# 13.net
KiCad netlist of a schematic drawn in Altium Designer
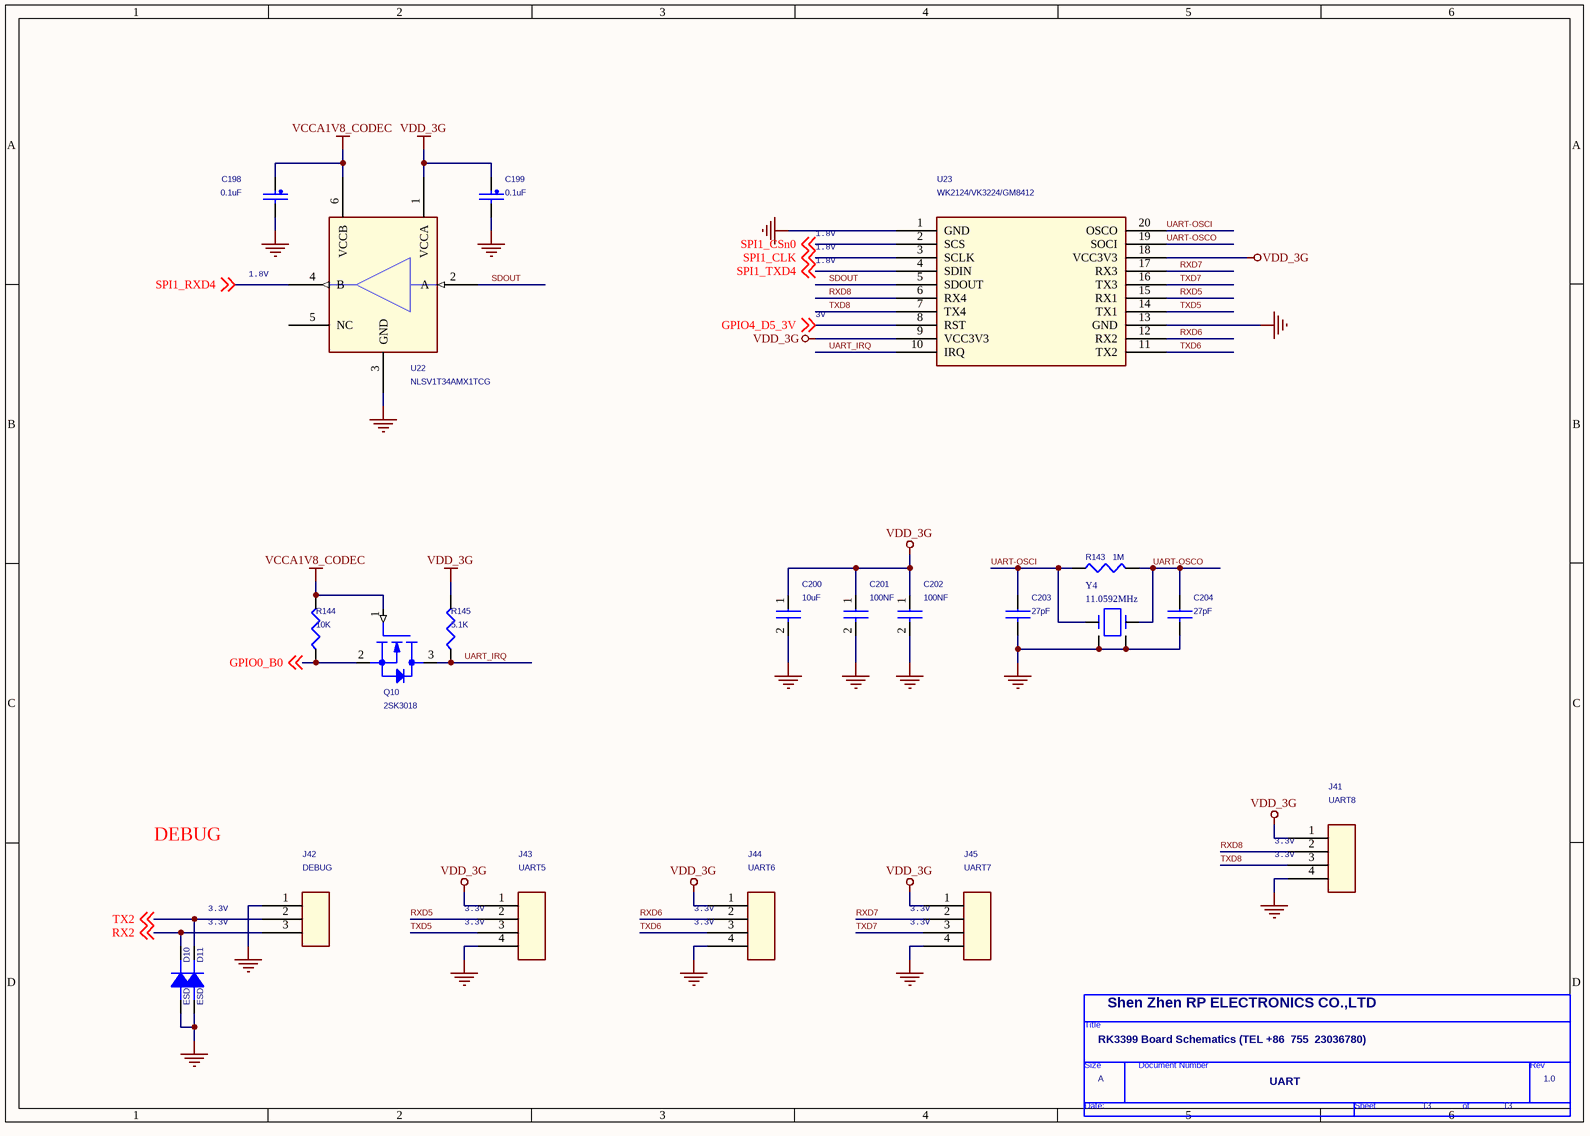
[diagram p0: 13.SchDoc]

(export (version "E")
  (design (tool "Eeschema 10.0.6"))
  (components
    (comp (ref "C198")
      (value "0.1uF")
      (description "CAP CER 0.22UF 6.3V 20% X5R 0201")
      (fields (field (name "TOLERANCE") "20%") (field (name "VOLTAGE") "6.3V"))
      (libsource (lib "*") (part "CAP_NP"))
    )
    (comp (ref "C199")
      (value "0.1uF")
      (description "CAP CER 0.22UF 10V 20% X5R 0201")
      (fields (field (name "VOLTAGE") "10V") (field (name "TOLERANCE") "20%"))
      (libsource (lib "*") (part "CAP_NP"))
    )
    (comp (ref "C200")
      (value "10uF")
      (footprint "0805C")
      (description "cap,10.00uF,+/-10%,10V,X5R,C0805")
      (fields
        (field (name "VOLTAGE") "10V")
        (field (name "TOLERANCE") "10%")
        (field (name "CREATED BY") "JJJ")
      )
      (libsource (lib "*") (part "CAP NP_Dup2"))
    )
    (comp (ref "C201")
      (value "100NF")
      (description "cap,100.00nF,+/-10%,16V,X5R,C0402")
      (fields
        (field (name "VOLTAGE") "16V")
        (field (name "MANUFACTURER") "TDK")
        (field (name "CREATED BY") "JJJ")
      )
      (libsource (lib "*") (part "CAP NP_Dup2"))
    )
    (comp (ref "C202")
      (value "100NF")
      (description "cap,100.00nF,+/-10%,16V,X5R,C0402")
      (fields
        (field (name "VOLTAGE") "16V")
        (field (name "MANUFACTURER") "TDK")
        (field (name "CREATED BY") "JJJ")
      )
      (libsource (lib "*") (part "CAP NP_Dup2"))
    )
    (comp (ref "C203") (value "27pF") (libsource (lib "*") (part "CAP NP_3_Dup1")))
    (comp (ref "C204") (value "27pF") (libsource (lib "*") (part "CAP NP_3_Dup1")))
    (comp (ref "D10") (value "ESD") (libsource (lib "*") (part "DIODE_Dup2")))
    (comp (ref "D11") (value "ESD") (libsource (lib "*") (part "DIODE_Dup2")))
    (comp (ref "J41") (value "UART8") (libsource (lib "*") (part "CON4")))
    (comp (ref "J42") (value "DEBUG") (libsource (lib "*") (part "CON4_1")))
    (comp (ref "J43") (value "UART5") (libsource (lib "*") (part "CON4")))
    (comp (ref "J44") (value "UART6") (libsource (lib "*") (part "CON4")))
    (comp (ref "J45") (value "UART7") (libsource (lib "*") (part "CON4")))
    (comp (ref "Q10") (value "2SK3018") (libsource (lib "*") (part "2N6756_0")))
    (comp (ref "R143") (value "1M") (footprint "0805") (libsource (lib "*") (part "RES_0")))
    (comp (ref "R144") (value "10K") (libsource (lib "*") (part "R_Dup1")))
    (comp (ref "R145") (value "5.1K") (libsource (lib "*") (part "R_Dup1")))
    (comp (ref "U22")
      (value "NLSV1T34AMX1TCG")
      (description "IC VXLTR 1 BIT DUAL-SUPPLY 0.9-4.5V 613AF")
      (libsource (lib "*") (part "NLSV1T34"))
    )
    (comp (ref "U23") (value "WK2124/VK3224/GM8412") (libsource (lib "*") (part "WK2124/VK3224/GM8412")))
    (comp (ref "Y4") (value "11.0592MHz") (libsource (lib "*") (part "CRYSTAL_2")))
  )
  (nets
    (net (code "1") (name "/RXD5") (class "Default")
      (node (ref "J43") (pin "2") (pinfunction "2_2") (pintype "passive"))
      (node (ref "U23") (pin "15") (pinfunction "RX1_15") (pintype "passive"))
    )
    (net (code "2") (name "/RXD6") (class "Default")
      (node (ref "J44") (pin "2") (pinfunction "2_2") (pintype "passive"))
      (node (ref "U23") (pin "12") (pinfunction "RX2_12") (pintype "passive"))
    )
    (net (code "3") (name "/RXD7") (class "Default")
      (node (ref "J45") (pin "2") (pinfunction "2_2") (pintype "passive"))
      (node (ref "U23") (pin "17") (pinfunction "RX3_17") (pintype "passive"))
    )
    (net (code "4") (name "/RXD8") (class "Default")
      (node (ref "J41") (pin "2") (pinfunction "2_2") (pintype "passive"))
      (node (ref "U23") (pin "6") (pinfunction "RX4_6") (pintype "passive"))
    )
    (net (code "5") (name "/SDOUT") (class "Default")
      (node (ref "U22") (pin "2") (pinfunction "A_2") (pintype "input"))
      (node (ref "U23") (pin "5") (pinfunction "SDOUT_5") (pintype "passive"))
    )
    (net (code "6") (name "/TXD5") (class "Default")
      (node (ref "J43") (pin "3") (pinfunction "3_3") (pintype "passive"))
      (node (ref "U23") (pin "14") (pinfunction "TX1_14") (pintype "passive"))
    )
    (net (code "7") (name "/TXD6") (class "Default")
      (node (ref "J44") (pin "3") (pinfunction "3_3") (pintype "passive"))
      (node (ref "U23") (pin "11") (pinfunction "TX2_11") (pintype "passive"))
    )
    (net (code "8") (name "/TXD7") (class "Default")
      (node (ref "J45") (pin "3") (pinfunction "3_3") (pintype "passive"))
      (node (ref "U23") (pin "16") (pinfunction "TX3_16") (pintype "passive"))
    )
    (net (code "9") (name "/TXD8") (class "Default")
      (node (ref "J41") (pin "3") (pinfunction "3_3") (pintype "passive"))
      (node (ref "U23") (pin "7") (pinfunction "TX4_7") (pintype "passive"))
    )
    (net (code "10") (name "/UART-OSCI") (class "Default")
      (node (ref "C203") (pin "1") (pinfunction "1_1") (pintype "passive"))
      (node (ref "R143") (pin "2") (pinfunction "2_2") (pintype "passive"))
      (node (ref "U23") (pin "20") (pinfunction "OSCO_20") (pintype "passive"))
      (node (ref "Y4") (pin "1") (pinfunction "1_1") (pintype "passive"))
    )
    (net (code "11") (name "/UART-OSCO") (class "Default")
      (node (ref "C204") (pin "1") (pinfunction "1_1") (pintype "passive"))
      (node (ref "R143") (pin "1") (pinfunction "1_1") (pintype "passive"))
      (node (ref "U23") (pin "19") (pinfunction "SOCI_19") (pintype "passive"))
      (node (ref "Y4") (pin "3") (pinfunction "3_3") (pintype "passive"))
    )
    (net (code "12") (name "/UART_IRQ") (class "Default")
      (node (ref "Q10") (pin "3") (pinfunction "DRAIN_3") (pintype "passive"))
      (node (ref "R145") (pin "2") (pinfunction "2_2") (pintype "passive"))
      (node (ref "U23") (pin "10") (pinfunction "IRQ_10") (pintype "passive"))
    )
    (net (code "13") (name "GND") (class "Default")
      (node (ref "C198") (pin "2") (pinfunction "2_2") (pintype "passive"))
      (node (ref "C199") (pin "2") (pinfunction "2_2") (pintype "passive"))
      (node (ref "C200") (pin "2") (pinfunction "2_2") (pintype "passive"))
      (node (ref "C201") (pin "2") (pinfunction "2_2") (pintype "passive"))
      (node (ref "C202") (pin "2") (pinfunction "2_2") (pintype "passive"))
      (node (ref "C203") (pin "2") (pinfunction "2_2") (pintype "passive"))
      (node (ref "C204") (pin "2") (pinfunction "2_2") (pintype "passive"))
      (node (ref "D10") (pin "1") (pinfunction "A_1") (pintype "passive"))
      (node (ref "D11") (pin "1") (pinfunction "A_1") (pintype "passive"))
      (node (ref "J41") (pin "4") (pinfunction "4_4") (pintype "passive"))
      (node (ref "J42") (pin "1") (pinfunction "1_1") (pintype "passive"))
      (node (ref "J43") (pin "4") (pinfunction "4_4") (pintype "passive"))
      (node (ref "J44") (pin "4") (pinfunction "4_4") (pintype "passive"))
      (node (ref "J45") (pin "4") (pinfunction "4_4") (pintype "passive"))
      (node (ref "U22") (pin "3") (pinfunction "GND_3") (pintype "power_in"))
      (node (ref "U23") (pin "1") (pinfunction "GND_1") (pintype "power_in"))
      (node (ref "U23") (pin "13") (pinfunction "GND_13") (pintype "power_in"))
      (node (ref "Y4") (pin "2") (pinfunction "2_2") (pintype "passive"))
      (node (ref "Y4") (pin "4") (pinfunction "4_4") (pintype "passive"))
    )
    (net (code "14") (name "GPIO0_B0") (class "Default")
      (node (ref "Q10") (pin "2") (pinfunction "SOURCE_2") (pintype "passive"))
      (node (ref "R144") (pin "2") (pinfunction "2_2") (pintype "passive"))
    )
    (net (code "15") (name "GPIO4_D5_3V") (class "Default")
      (node (ref "U23") (pin "8") (pinfunction "RST_8") (pintype "passive"))
    )
    (net (code "16") (name "RX2") (class "Default")
      (node (ref "D10") (pin "2") (pinfunction "K_2") (pintype "passive"))
      (node (ref "J42") (pin "3") (pinfunction "3_3") (pintype "passive"))
    )
    (net (code "17") (name "SPI1_CLK") (class "Default")
      (node (ref "U23") (pin "3") (pinfunction "SCLK_3") (pintype "passive"))
    )
    (net (code "18") (name "SPI1_CSn0") (class "Default")
      (node (ref "U23") (pin "2") (pinfunction "SCS_2") (pintype "passive"))
    )
    (net (code "19") (name "SPI1_RXD4") (class "Default")
      (node (ref "U22") (pin "4") (pinfunction "B_4") (pintype "output"))
    )
    (net (code "20") (name "SPI1_TXD4") (class "Default")
      (node (ref "U23") (pin "4") (pinfunction "SDIN_4") (pintype "passive"))
    )
    (net (code "21") (name "TX2") (class "Default")
      (node (ref "D11") (pin "2") (pinfunction "K_2") (pintype "passive"))
      (node (ref "J42") (pin "2") (pinfunction "2_2") (pintype "passive"))
    )
    (net (code "22") (name "VCCA1V8_CODEC") (class "Default")
      (node (ref "C198") (pin "1") (pinfunction "1_1") (pintype "passive"))
      (node (ref "Q10") (pin "1") (pinfunction "GATE_1") (pintype "input"))
      (node (ref "R144") (pin "1") (pinfunction "1_1") (pintype "passive"))
      (node (ref "U22") (pin "6") (pinfunction "VCCB_6") (pintype "power_in"))
    )
    (net (code "23") (name "VDD_3G") (class "Default")
      (node (ref "C199") (pin "1") (pinfunction "1_1") (pintype "passive"))
      (node (ref "C200") (pin "1") (pinfunction "1_1") (pintype "passive"))
      (node (ref "C201") (pin "1") (pinfunction "1_1") (pintype "passive"))
      (node (ref "C202") (pin "1") (pinfunction "1_1") (pintype "passive"))
      (node (ref "J41") (pin "1") (pinfunction "1_1") (pintype "passive"))
      (node (ref "J43") (pin "1") (pinfunction "1_1") (pintype "passive"))
      (node (ref "J44") (pin "1") (pinfunction "1_1") (pintype "passive"))
      (node (ref "J45") (pin "1") (pinfunction "1_1") (pintype "passive"))
      (node (ref "R145") (pin "1") (pinfunction "1_1") (pintype "passive"))
      (node (ref "U22") (pin "1") (pinfunction "VCCA_1") (pintype "power_in"))
      (node (ref "U23") (pin "18") (pinfunction "VCC3V3_18") (pintype "power_in"))
      (node (ref "U23") (pin "9") (pinfunction "VCC3V3_9") (pintype "power_in"))
    )
    (net (code "24") (name "unconnected-(U22-NC-Pad5)") (class "Default")
      (node (ref "U22") (pin "5") (pinfunction "NC_5") (pintype "passive"))
    )
  )
)
